# HDC2022.net
KiCad netlist of a schematic drawn in Altium Designer
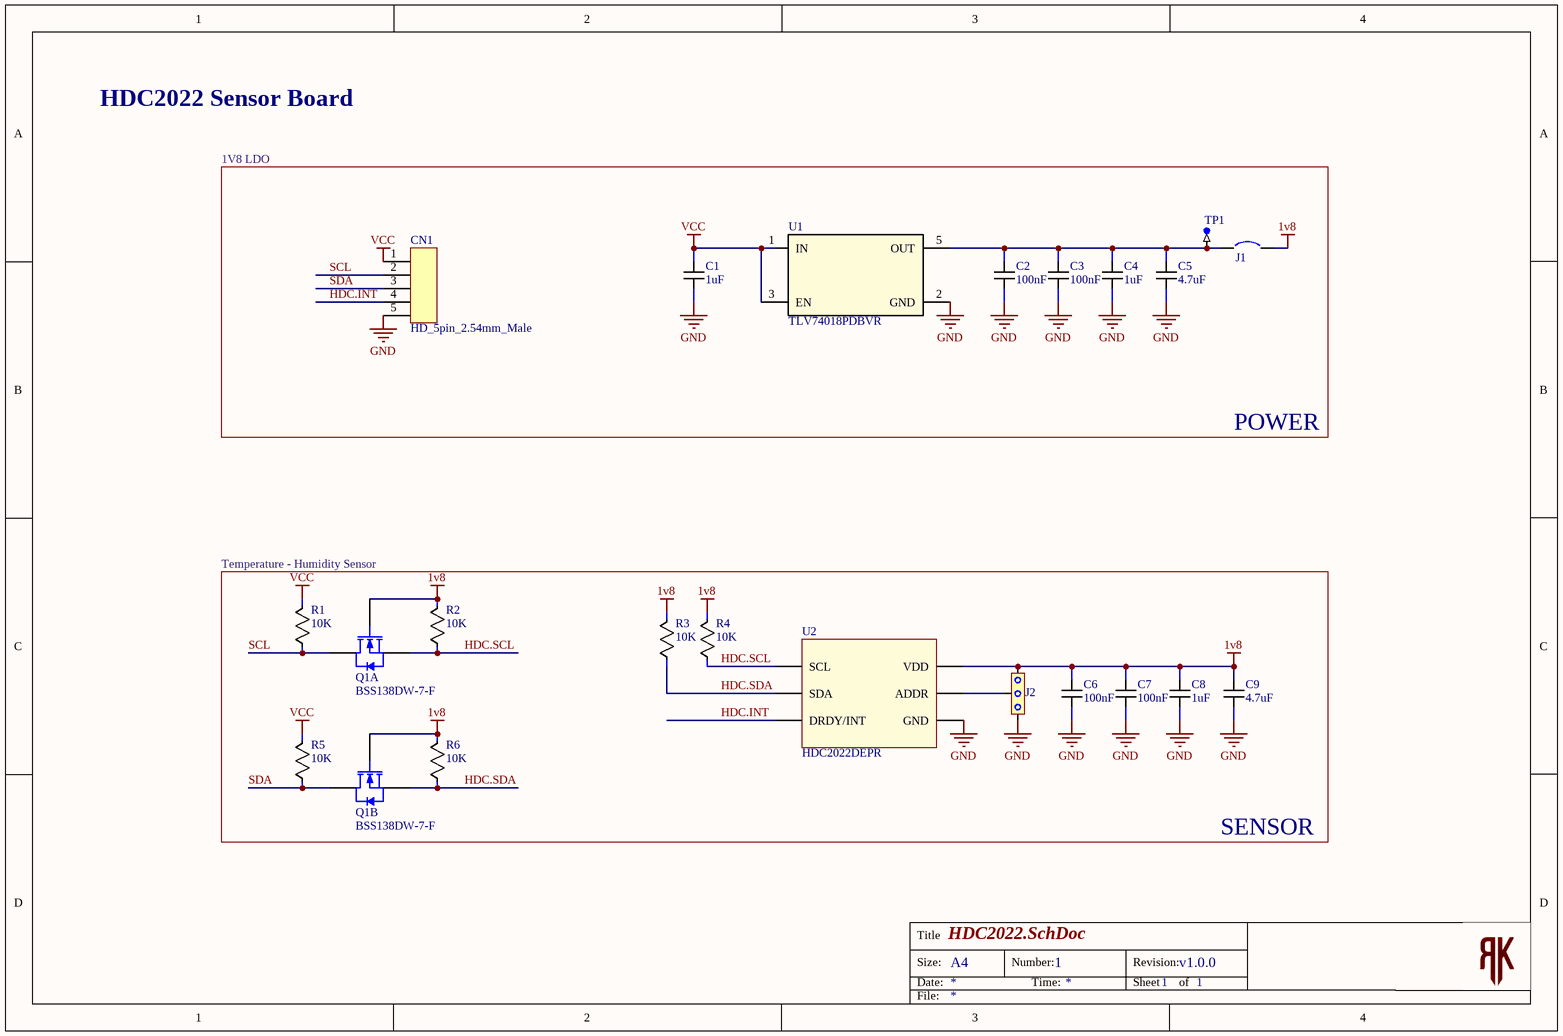
[diagram p0: HDC2022.SchDoc]

(export (version "E")
  (design (tool "Eeschema 10.0.6"))
  (components
    (comp (ref "C1") (value "1uF") (footprint "CAP_0603") (libsource (lib "HDC2022") (part "Capacitor")))
    (comp (ref "C2") (value "100nF") (footprint "CAP_0603") (libsource (lib "HDC2022") (part "Capacitor")))
    (comp (ref "C3") (value "100nF") (footprint "CAP_0603") (libsource (lib "HDC2022") (part "Capacitor")))
    (comp (ref "C4") (value "1uF") (footprint "CAP_0603") (libsource (lib "HDC2022") (part "Capacitor")))
    (comp (ref "C5") (value "4.7uF") (footprint "CAP_0603") (libsource (lib "HDC2022") (part "Capacitor")))
    (comp (ref "C6") (value "100nF") (footprint "CAP_0603") (libsource (lib "HDC2022") (part "Capacitor")))
    (comp (ref "C7") (value "100nF") (footprint "CAP_0603") (libsource (lib "HDC2022") (part "Capacitor")))
    (comp (ref "C8") (value "1uF") (footprint "CAP_0603") (libsource (lib "HDC2022") (part "Capacitor")))
    (comp (ref "C9") (value "4.7uF") (footprint "CAP_0603") (libsource (lib "HDC2022") (part "Capacitor")))
    (comp (ref "CN1")
      (value "HD_5pin_2.54mm_Male")
      (footprint "HD_5pin_2.54mm_male")
      (libsource (lib "HDC2022") (part "HD_5pin_2.54mm_Male"))
    )
    (comp (ref "J1")
      (value "Jumper")
      (footprint "SB_0603")
      (fields (field (name "PUBLISHER") "Altium Limited"))
      (libsource (lib "HDC2022") (part "Jumper"))
    )
    (comp (ref "J2")
      (value "JUMPER_3Pin")
      (footprint "SB_0603 - 3 Pin")
      (libsource (lib "HDC2022") (part "JUMPER_3Pin"))
    )
    (comp (ref "Q1")
      (value "BSS138DW-7-F")
      (footprint "DIOD-SOT363-6_V")
      (fields (field (name "MANUFACTURER") "DiodesIncorporated"))
      (libsource (lib "HDC2022") (part "CMP-2000-05966-2"))
    )
    (comp (ref "R1") (value "10K") (footprint "RES_0603") (libsource (lib "HDC2022") (part "Resistor")))
    (comp (ref "R2") (value "10K") (footprint "RES_0603") (libsource (lib "HDC2022") (part "Resistor")))
    (comp (ref "R3") (value "10K") (footprint "RES_0603") (libsource (lib "HDC2022") (part "Resistor")))
    (comp (ref "R4") (value "10K") (footprint "RES_0603") (libsource (lib "HDC2022") (part "Resistor")))
    (comp (ref "R5") (value "10K") (footprint "RES_0603") (libsource (lib "HDC2022") (part "Resistor")))
    (comp (ref "R6") (value "10K") (footprint "RES_0603") (libsource (lib "HDC2022") (part "Resistor")))
    (comp (ref "TP1") (value "Test Point") (footprint "TP") (libsource (lib "HDC2022") (part "Test Point")))
    (comp (ref "U1")
      (value "TLV74018PDBVR")
      (footprint "SOIC_DBVR_TEX")
      (fields (field (name "MANUFACTURER") "Texas Instruments"))
      (libsource (lib "HDC2022") (part "TLV74018PDBVR"))
    )
    (comp (ref "U2")
      (value "HDC2022DEPR")
      (footprint "WSON-6")
      (fields (field (name "MANUFACTURER") "Texas Instruments"))
      (libsource (lib "HDC2022") (part "HDC2022DEPR"))
    )
  )
  (nets
    (net (code "1") (name "/HDC.INT") (class "Default")
      (node (ref "CN1") (pin "4") (pinfunction "4_4") (pintype "passive"))
      (node (ref "U2") (pin "4") (pinfunction "DRDY/INT_4") (pintype "passive"))
    )
    (net (code "2") (name "/HDC.SCL") (class "Default")
      (node (ref "Q1") (pin "1") (pinfunction "S1_1") (pintype "passive"))
      (node (ref "R2") (pin "1") (pinfunction "1_1") (pintype "passive"))
      (node (ref "R4") (pin "1") (pinfunction "1_1") (pintype "passive"))
      (node (ref "U2") (pin "6") (pinfunction "SCL_6") (pintype "passive"))
    )
    (net (code "3") (name "/HDC.SDA") (class "Default")
      (node (ref "Q1") (pin "4") (pinfunction "S2_4") (pintype "passive"))
      (node (ref "R3") (pin "1") (pinfunction "1_1") (pintype "passive"))
      (node (ref "R6") (pin "1") (pinfunction "1_1") (pintype "passive"))
      (node (ref "U2") (pin "1") (pinfunction "SDA_1") (pintype "passive"))
    )
    (net (code "4") (name "/SCL") (class "Default")
      (node (ref "CN1") (pin "2") (pinfunction "2_2") (pintype "passive"))
      (node (ref "Q1") (pin "6") (pinfunction "D1_6") (pintype "passive"))
      (node (ref "R1") (pin "1") (pinfunction "1_1") (pintype "passive"))
    )
    (net (code "5") (name "/SDA") (class "Default")
      (node (ref "CN1") (pin "3") (pinfunction "3_3") (pintype "passive"))
      (node (ref "Q1") (pin "3") (pinfunction "D2_3") (pintype "passive"))
      (node (ref "R5") (pin "1") (pinfunction "1_1") (pintype "passive"))
    )
    (net (code "6") (name "1v8") (class "Default")
      (node (ref "C6") (pin "2") (pinfunction "2_2") (pintype "passive"))
      (node (ref "C7") (pin "2") (pinfunction "2_2") (pintype "passive"))
      (node (ref "C8") (pin "2") (pinfunction "2_2") (pintype "passive"))
      (node (ref "C9") (pin "2") (pinfunction "2_2") (pintype "passive"))
      (node (ref "J1") (pin "2") (pinfunction "2_2") (pintype "passive"))
      (node (ref "J2") (pin "1") (pinfunction "1_1") (pintype "passive"))
      (node (ref "Q1") (pin "2") (pinfunction "G1_2") (pintype "passive"))
      (node (ref "Q1") (pin "5") (pinfunction "G2_5") (pintype "passive"))
      (node (ref "R2") (pin "2") (pinfunction "2_2") (pintype "passive"))
      (node (ref "R3") (pin "2") (pinfunction "2_2") (pintype "passive"))
      (node (ref "R4") (pin "2") (pinfunction "2_2") (pintype "passive"))
      (node (ref "R6") (pin "2") (pinfunction "2_2") (pintype "passive"))
      (node (ref "U2") (pin "5") (pinfunction "VDD_5") (pintype "passive"))
    )
    (net (code "7") (name "GND") (class "Default")
      (node (ref "C1") (pin "1") (pinfunction "1_1") (pintype "passive"))
      (node (ref "C2") (pin "1") (pinfunction "1_1") (pintype "passive"))
      (node (ref "C3") (pin "1") (pinfunction "1_1") (pintype "passive"))
      (node (ref "C4") (pin "1") (pinfunction "1_1") (pintype "passive"))
      (node (ref "C5") (pin "1") (pinfunction "1_1") (pintype "passive"))
      (node (ref "C6") (pin "1") (pinfunction "1_1") (pintype "passive"))
      (node (ref "C7") (pin "1") (pinfunction "1_1") (pintype "passive"))
      (node (ref "C8") (pin "1") (pinfunction "1_1") (pintype "passive"))
      (node (ref "C9") (pin "1") (pinfunction "1_1") (pintype "passive"))
      (node (ref "CN1") (pin "5") (pinfunction "5_5") (pintype "passive"))
      (node (ref "J2") (pin "3") (pinfunction "3_3") (pintype "passive"))
      (node (ref "U1") (pin "2") (pinfunction "GND_2") (pintype "passive"))
      (node (ref "U2") (pin "2") (pinfunction "GND_2") (pintype "passive"))
    )
    (net (code "8") (name "Net-(U1-OUT)") (class "Default")
      (node (ref "C2") (pin "2") (pinfunction "2_2") (pintype "passive"))
      (node (ref "C3") (pin "2") (pinfunction "2_2") (pintype "passive"))
      (node (ref "C4") (pin "2") (pinfunction "2_2") (pintype "passive"))
      (node (ref "C5") (pin "2") (pinfunction "2_2") (pintype "passive"))
      (node (ref "J1") (pin "1") (pinfunction "1_1") (pintype "passive"))
      (node (ref "TP1") (pin "1") (pinfunction "1_1") (pintype "input"))
      (node (ref "U1") (pin "5") (pinfunction "OUT_5") (pintype "passive"))
    )
    (net (code "9") (name "Net-(U2-ADDR)") (class "Default")
      (node (ref "J2") (pin "2") (pinfunction "2_2") (pintype "passive"))
      (node (ref "U2") (pin "3") (pinfunction "ADDR_3") (pintype "passive"))
    )
    (net (code "10") (name "VCC") (class "Default")
      (node (ref "C1") (pin "2") (pinfunction "2_2") (pintype "passive"))
      (node (ref "CN1") (pin "1") (pinfunction "1_1") (pintype "passive"))
      (node (ref "R1") (pin "2") (pinfunction "2_2") (pintype "passive"))
      (node (ref "R5") (pin "2") (pinfunction "2_2") (pintype "passive"))
      (node (ref "U1") (pin "1") (pinfunction "IN_1") (pintype "passive"))
      (node (ref "U1") (pin "3") (pinfunction "EN_3") (pintype "passive"))
    )
    (net (code "11") (name "unconnected-(U1-NC-Pad4)") (class "Default")
      (node (ref "U1") (pin "4") (pinfunction "NC_4") (pintype "passive"))
    )
  )
)
